# Sheet1_Overview.net
KiCad netlist of a schematic drawn in Altium Designer
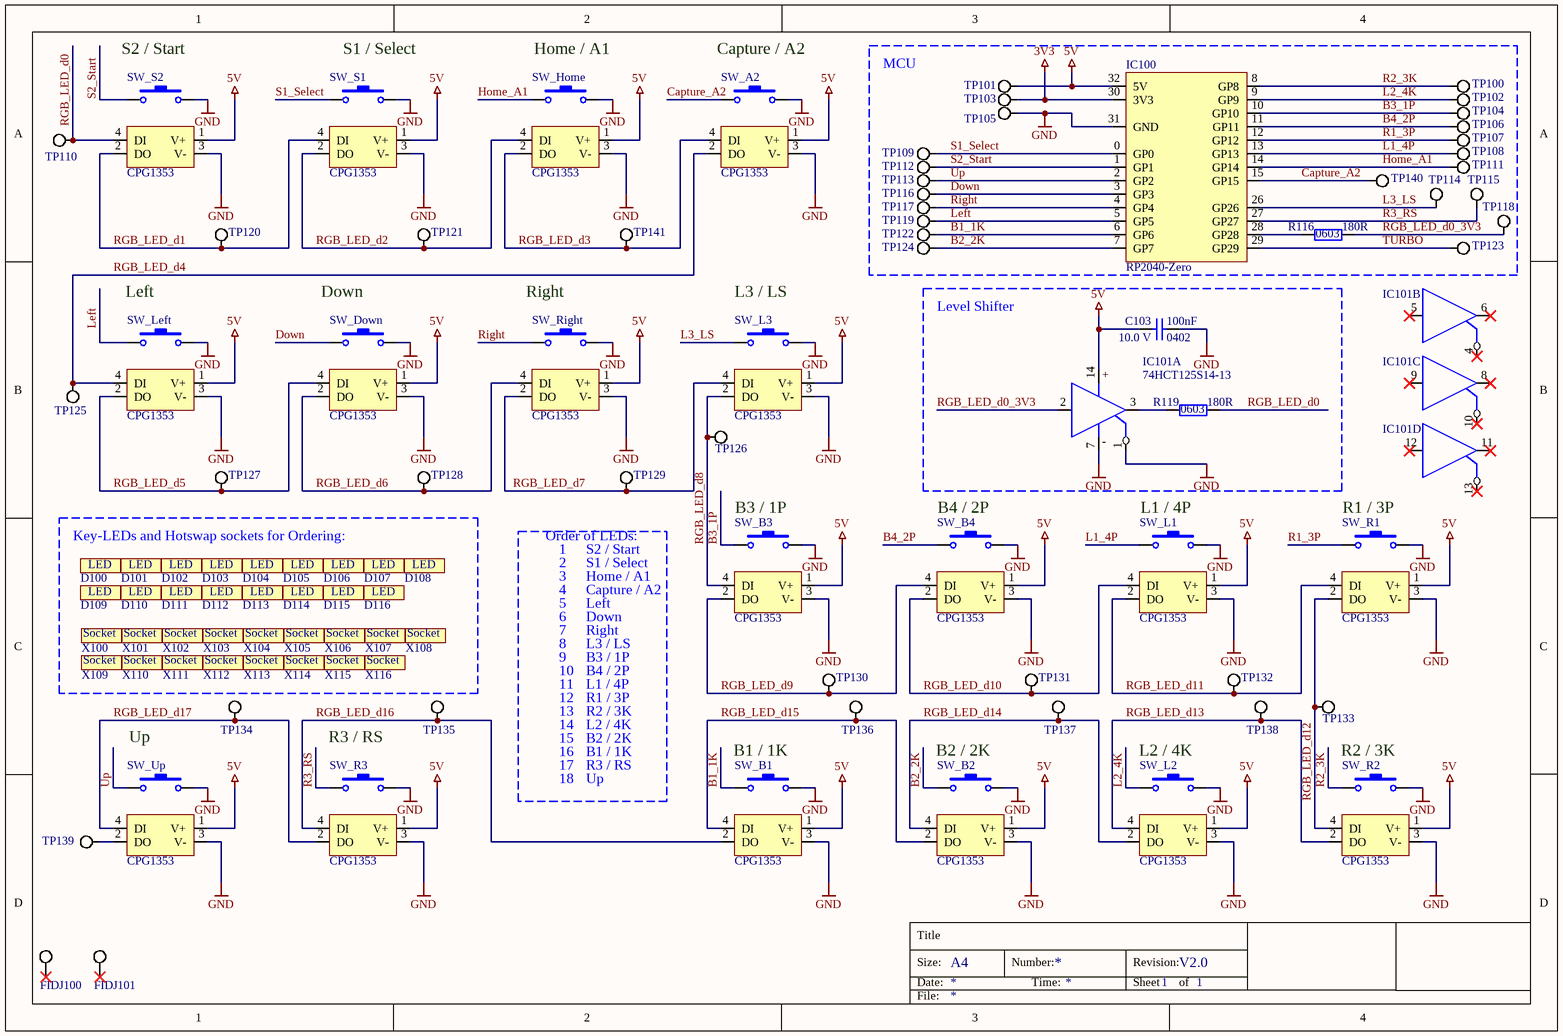
[diagram p0: Sheet1_Overview.SchDoc]

(export (version "E")
  (design (tool "Eeschema 10.0.6"))
  (components
    (comp (ref "C103")
      (value "C 100nF 0402 10V")
      (footprint "0402")
      (description "CAP CER 0.1UF 10V X5R 0402")
      (fields
        (field (name "MANUFACTURER") "Samsung Electro-Mechanics")
        (field (name "MANUFACTURER PART NUMBER") "CL05A104MP5NNNC")
        (field (name "CAPACITANCE") "100nF")
        (field (name "VOLTAGE") "10.0 V")
      )
      (libsource (lib "CS_Part_Library") (part "CAP_100nF_10V_0402"))
    )
    (comp (ref "D100")
      (value "LED RGB")
      (description "LED for SW_CPG1353")
      (fields (field (name "MANUFACTURER") "Opsco") (field (name "MANUFACTURER PART NUMBER") "SK6812Mini-E"))
      (libsource (lib "Symbols") (part "SW_CPG1353_LED"))
    )
    (comp (ref "D101")
      (value "LED RGB")
      (description "LED for SW_CPG1353")
      (fields (field (name "MANUFACTURER") "Opsco") (field (name "MANUFACTURER PART NUMBER") "SK6812Mini-E"))
      (libsource (lib "Symbols") (part "SW_CPG1353_LED"))
    )
    (comp (ref "D102")
      (value "LED RGB")
      (description "LED for SW_CPG1353")
      (fields (field (name "MANUFACTURER") "Opsco") (field (name "MANUFACTURER PART NUMBER") "SK6812Mini-E"))
      (libsource (lib "Symbols") (part "SW_CPG1353_LED"))
    )
    (comp (ref "D103")
      (value "LED RGB")
      (description "LED for SW_CPG1353")
      (fields (field (name "MANUFACTURER") "Opsco") (field (name "MANUFACTURER PART NUMBER") "SK6812Mini-E"))
      (libsource (lib "Symbols") (part "SW_CPG1353_LED"))
    )
    (comp (ref "D104")
      (value "LED RGB")
      (description "LED for SW_CPG1353")
      (fields (field (name "MANUFACTURER") "Opsco") (field (name "MANUFACTURER PART NUMBER") "SK6812Mini-E"))
      (libsource (lib "Symbols") (part "SW_CPG1353_LED"))
    )
    (comp (ref "D105")
      (value "LED RGB")
      (description "LED for SW_CPG1353")
      (fields (field (name "MANUFACTURER") "Opsco") (field (name "MANUFACTURER PART NUMBER") "SK6812Mini-E"))
      (libsource (lib "Symbols") (part "SW_CPG1353_LED"))
    )
    (comp (ref "D106")
      (value "LED RGB")
      (description "LED for SW_CPG1353")
      (fields (field (name "MANUFACTURER") "Opsco") (field (name "MANUFACTURER PART NUMBER") "SK6812Mini-E"))
      (libsource (lib "Symbols") (part "SW_CPG1353_LED"))
    )
    (comp (ref "D107")
      (value "LED RGB")
      (description "LED for SW_CPG1353")
      (fields (field (name "MANUFACTURER") "Opsco") (field (name "MANUFACTURER PART NUMBER") "SK6812Mini-E"))
      (libsource (lib "Symbols") (part "SW_CPG1353_LED"))
    )
    (comp (ref "D108")
      (value "LED RGB")
      (description "LED for SW_CPG1353")
      (fields (field (name "MANUFACTURER") "Opsco") (field (name "MANUFACTURER PART NUMBER") "SK6812Mini-E"))
      (libsource (lib "Symbols") (part "SW_CPG1353_LED"))
    )
    (comp (ref "D109")
      (value "LED RGB")
      (description "LED for SW_CPG1353")
      (fields (field (name "MANUFACTURER") "Opsco") (field (name "MANUFACTURER PART NUMBER") "SK6812Mini-E"))
      (libsource (lib "Symbols") (part "SW_CPG1353_LED"))
    )
    (comp (ref "D110")
      (value "LED RGB")
      (description "LED for SW_CPG1353")
      (fields (field (name "MANUFACTURER") "Opsco") (field (name "MANUFACTURER PART NUMBER") "SK6812Mini-E"))
      (libsource (lib "Symbols") (part "SW_CPG1353_LED"))
    )
    (comp (ref "D111")
      (value "LED RGB")
      (description "LED for SW_CPG1353")
      (fields (field (name "MANUFACTURER") "Opsco") (field (name "MANUFACTURER PART NUMBER") "SK6812Mini-E"))
      (libsource (lib "Symbols") (part "SW_CPG1353_LED"))
    )
    (comp (ref "D112")
      (value "LED RGB")
      (description "LED for SW_CPG1353")
      (fields (field (name "MANUFACTURER") "Opsco") (field (name "MANUFACTURER PART NUMBER") "SK6812Mini-E"))
      (libsource (lib "Symbols") (part "SW_CPG1353_LED"))
    )
    (comp (ref "D113")
      (value "LED RGB")
      (description "LED for SW_CPG1353")
      (fields (field (name "MANUFACTURER") "Opsco") (field (name "MANUFACTURER PART NUMBER") "SK6812Mini-E"))
      (libsource (lib "Symbols") (part "SW_CPG1353_LED"))
    )
    (comp (ref "D114")
      (value "LED RGB")
      (description "LED for SW_CPG1353")
      (fields (field (name "MANUFACTURER") "Opsco") (field (name "MANUFACTURER PART NUMBER") "SK6812Mini-E"))
      (libsource (lib "Symbols") (part "SW_CPG1353_LED"))
    )
    (comp (ref "D115")
      (value "LED RGB")
      (description "LED for SW_CPG1353")
      (fields (field (name "MANUFACTURER") "Opsco") (field (name "MANUFACTURER PART NUMBER") "SK6812Mini-E"))
      (libsource (lib "Symbols") (part "SW_CPG1353_LED"))
    )
    (comp (ref "D116")
      (value "LED RGB")
      (description "LED for SW_CPG1353")
      (fields (field (name "MANUFACTURER") "Opsco") (field (name "MANUFACTURER PART NUMBER") "SK6812Mini-E"))
      (libsource (lib "Symbols") (part "SW_CPG1353_LED"))
    )
    (comp (ref "FIDJ100")
      (value "Fiducial")
      (footprint "FIDJ_1mm")
      (description "Fiducal 1mm")
      (libsource (lib "CS_Part_Library") (part "FIDJ_1mm"))
    )
    (comp (ref "FIDJ101")
      (value "Fiducial")
      (footprint "FIDJ_1mm")
      (description "Fiducal 1mm")
      (libsource (lib "CS_Part_Library") (part "FIDJ_1mm"))
    )
    (comp (ref "IC100")
      (value "RP2040-Zero")
      (footprint "IC_RP2040-Zero")
      (description "Waveshare RP2040-Zero Module")
      (fields (field (name "MANUFACTURER") "Waveshare"))
      (libsource (lib "CS_Part_Library") (part "IC_RP2040-Zero"))
    )
    (comp (ref "IC101")
      (value "74HCT125S14-13")
      (footprint "SOIC-14")
      (description "IC BUFFER NON-INVERT 5.5V 14SO")
      (fields (field (name "MANUFACTURER") "Diodes Incorporated"))
      (libsource (lib "CS_Part_Library") (part "IC_Logic_1BUF_4CH"))
    )
    (comp (ref "R116")
      (value "R 180R 0603")
      (footprint "0603")
      (description "RES 180 OHM 1% 1/10W 0603")
      (fields
        (field (name "MANUFACTURER") "Stackpole Electronics Inc")
        (field (name "MANUFACTURER PART NUMBER") "RMCF0603FT180R")
        (field (name "RESISTANCE") "180R")
      )
      (libsource (lib "CS_Part_Library") (part "R_180R_0603"))
    )
    (comp (ref "R119")
      (value "R 180R 0603")
      (footprint "0603")
      (description "RES 180 OHM 1% 1/10W 0603")
      (fields
        (field (name "MANUFACTURER") "Stackpole Electronics Inc")
        (field (name "MANUFACTURER PART NUMBER") "RMCF0603FT180R")
        (field (name "RESISTANCE") "180R")
      )
      (libsource (lib "CS_Part_Library") (part "R_180R_0603"))
    )
    (comp (ref "SW_A2")
      (value "CPG1353")
      (footprint "SW_Kailh_CPG1353")
      (description "Kailh Choc low profile switches V2 (CPG1353) /w Hotswap, LED")
      (fields (field (name "MANUFACTURER") "Kailh"))
      (libsource (lib "CS_Part_Library") (part "SW_CPG1353_HS_LED"))
    )
    (comp (ref "SW_B1")
      (value "CPG1353")
      (footprint "SW_Kailh_CPG1353")
      (description "Kailh Choc low profile switches V2 (CPG1353) /w Hotswap, LED")
      (fields (field (name "MANUFACTURER") "Kailh"))
      (libsource (lib "CS_Part_Library") (part "SW_CPG1353_HS_LED"))
    )
    (comp (ref "SW_B2")
      (value "CPG1353")
      (footprint "SW_Kailh_CPG1353")
      (description "Kailh Choc low profile switches V2 (CPG1353) /w Hotswap, LED")
      (fields (field (name "MANUFACTURER") "Kailh"))
      (libsource (lib "CS_Part_Library") (part "SW_CPG1353_HS_LED"))
    )
    (comp (ref "SW_B3")
      (value "CPG1353")
      (footprint "SW_Kailh_CPG1353")
      (description "Kailh Choc low profile switches V2 (CPG1353) /w Hotswap, LED")
      (fields (field (name "MANUFACTURER") "Kailh"))
      (libsource (lib "CS_Part_Library") (part "SW_CPG1353_HS_LED"))
    )
    (comp (ref "SW_B4")
      (value "CPG1353")
      (footprint "SW_Kailh_CPG1353")
      (description "Kailh Choc low profile switches V2 (CPG1353) /w Hotswap, LED")
      (fields (field (name "MANUFACTURER") "Kailh"))
      (libsource (lib "CS_Part_Library") (part "SW_CPG1353_HS_LED"))
    )
    (comp (ref "SW_Down")
      (value "CPG1353")
      (footprint "SW_Kailh_CPG1353")
      (description "Kailh Choc low profile switches V2 (CPG1353) /w Hotswap, LED")
      (fields (field (name "MANUFACTURER") "Kailh"))
      (libsource (lib "CS_Part_Library") (part "SW_CPG1353_HS_LED"))
    )
    (comp (ref "SW_Home")
      (value "CPG1353")
      (footprint "SW_Kailh_CPG1353")
      (description "Kailh Choc low profile switches V2 (CPG1353) /w Hotswap, LED")
      (fields (field (name "MANUFACTURER") "Kailh"))
      (libsource (lib "CS_Part_Library") (part "SW_CPG1353_HS_LED"))
    )
    (comp (ref "SW_L1")
      (value "CPG1353")
      (footprint "SW_Kailh_CPG1353")
      (description "Kailh Choc low profile switches V2 (CPG1353) /w Hotswap, LED")
      (fields (field (name "MANUFACTURER") "Kailh"))
      (libsource (lib "CS_Part_Library") (part "SW_CPG1353_HS_LED"))
    )
    (comp (ref "SW_L2")
      (value "CPG1353")
      (footprint "SW_Kailh_CPG1353")
      (description "Kailh Choc low profile switches V2 (CPG1353) /w Hotswap, LED")
      (fields (field (name "MANUFACTURER") "Kailh"))
      (libsource (lib "CS_Part_Library") (part "SW_CPG1353_HS_LED"))
    )
    (comp (ref "SW_L3")
      (value "CPG1353")
      (footprint "SW_Kailh_CPG1353")
      (description "Kailh Choc low profile switches V2 (CPG1353) /w Hotswap, LED")
      (fields (field (name "MANUFACTURER") "Kailh"))
      (libsource (lib "CS_Part_Library") (part "SW_CPG1353_HS_LED"))
    )
    (comp (ref "SW_Left")
      (value "CPG1353")
      (footprint "SW_Kailh_CPG1353")
      (description "Kailh Choc low profile switches V2 (CPG1353) /w Hotswap, LED")
      (fields (field (name "MANUFACTURER") "Kailh"))
      (libsource (lib "CS_Part_Library") (part "SW_CPG1353_HS_LED"))
    )
    (comp (ref "SW_R1")
      (value "CPG1353")
      (footprint "SW_Kailh_CPG1353")
      (description "Kailh Choc low profile switches V2 (CPG1353) /w Hotswap, LED")
      (fields (field (name "MANUFACTURER") "Kailh"))
      (libsource (lib "CS_Part_Library") (part "SW_CPG1353_HS_LED"))
    )
    (comp (ref "SW_R2")
      (value "CPG1353")
      (footprint "SW_Kailh_CPG1353")
      (description "Kailh Choc low profile switches V2 (CPG1353) /w Hotswap, LED")
      (fields (field (name "MANUFACTURER") "Kailh"))
      (libsource (lib "CS_Part_Library") (part "SW_CPG1353_HS_LED"))
    )
    (comp (ref "SW_R3")
      (value "CPG1353")
      (footprint "SW_Kailh_CPG1353")
      (description "Kailh Choc low profile switches V2 (CPG1353) /w Hotswap, LED")
      (fields (field (name "MANUFACTURER") "Kailh"))
      (libsource (lib "CS_Part_Library") (part "SW_CPG1353_HS_LED"))
    )
    (comp (ref "SW_Right")
      (value "CPG1353")
      (footprint "SW_Kailh_CPG1353")
      (description "Kailh Choc low profile switches V2 (CPG1353) /w Hotswap, LED")
      (fields (field (name "MANUFACTURER") "Kailh"))
      (libsource (lib "CS_Part_Library") (part "SW_CPG1353_HS_LED"))
    )
    (comp (ref "SW_S1")
      (value "CPG1353")
      (footprint "SW_Kailh_CPG1353")
      (description "Kailh Choc low profile switches V2 (CPG1353) /w Hotswap, LED")
      (fields (field (name "MANUFACTURER") "Kailh"))
      (libsource (lib "CS_Part_Library") (part "SW_CPG1353_HS_LED"))
    )
    (comp (ref "SW_S2")
      (value "CPG1353")
      (footprint "SW_Kailh_CPG1353")
      (description "Kailh Choc low profile switches V2 (CPG1353) /w Hotswap, LED")
      (fields (field (name "MANUFACTURER") "Kailh"))
      (libsource (lib "CS_Part_Library") (part "SW_CPG1353_HS_LED"))
    )
    (comp (ref "SW_Up")
      (value "CPG1353")
      (footprint "SW_Kailh_CPG1353")
      (description "Kailh Choc low profile switches V2 (CPG1353) /w Hotswap, LED")
      (fields (field (name "MANUFACTURER") "Kailh"))
      (libsource (lib "CS_Part_Library") (part "SW_CPG1353_HS_LED"))
    )
    (comp (ref "TP100")
      (value "TP")
      (footprint "TP_1mm")
      (description "Test Point 1mm")
      (libsource (lib "CS_Part_Library") (part "TP_1mm"))
    )
    (comp (ref "TP101")
      (value "TP")
      (footprint "TP_1mm")
      (description "Test Point 1mm")
      (libsource (lib "CS_Part_Library") (part "TP_1mm"))
    )
    (comp (ref "TP102")
      (value "TP")
      (footprint "TP_1mm")
      (description "Test Point 1mm")
      (libsource (lib "CS_Part_Library") (part "TP_1mm"))
    )
    (comp (ref "TP103")
      (value "TP")
      (footprint "TP_1mm")
      (description "Test Point 1mm")
      (libsource (lib "CS_Part_Library") (part "TP_1mm"))
    )
    (comp (ref "TP104")
      (value "TP")
      (footprint "TP_1mm")
      (description "Test Point 1mm")
      (libsource (lib "CS_Part_Library") (part "TP_1mm"))
    )
    (comp (ref "TP105")
      (value "TP")
      (footprint "TP_1mm")
      (description "Test Point 1mm")
      (libsource (lib "CS_Part_Library") (part "TP_1mm"))
    )
    (comp (ref "TP106")
      (value "TP")
      (footprint "TP_1mm")
      (description "Test Point 1mm")
      (libsource (lib "CS_Part_Library") (part "TP_1mm"))
    )
    (comp (ref "TP107")
      (value "TP")
      (footprint "TP_1mm")
      (description "Test Point 1mm")
      (libsource (lib "CS_Part_Library") (part "TP_1mm"))
    )
    (comp (ref "TP108")
      (value "TP")
      (footprint "TP_1mm")
      (description "Test Point 1mm")
      (libsource (lib "CS_Part_Library") (part "TP_1mm"))
    )
    (comp (ref "TP109")
      (value "TP")
      (footprint "TP_1mm")
      (description "Test Point 1mm")
      (libsource (lib "CS_Part_Library") (part "TP_1mm"))
    )
    (comp (ref "TP110")
      (value "TP")
      (footprint "TP_1mm")
      (description "Test Point 1mm")
      (libsource (lib "CS_Part_Library") (part "TP_1mm"))
    )
    (comp (ref "TP111")
      (value "TP")
      (footprint "TP_1mm")
      (description "Test Point 1mm")
      (libsource (lib "CS_Part_Library") (part "TP_1mm"))
    )
    (comp (ref "TP112")
      (value "TP")
      (footprint "TP_1mm")
      (description "Test Point 1mm")
      (libsource (lib "CS_Part_Library") (part "TP_1mm"))
    )
    (comp (ref "TP113")
      (value "TP")
      (footprint "TP_1mm")
      (description "Test Point 1mm")
      (libsource (lib "CS_Part_Library") (part "TP_1mm"))
    )
    (comp (ref "TP114")
      (value "TP")
      (footprint "TP_1mm")
      (description "Test Point 1mm")
      (libsource (lib "CS_Part_Library") (part "TP_1mm"))
    )
    (comp (ref "TP115")
      (value "TP")
      (footprint "TP_1mm")
      (description "Test Point 1mm")
      (libsource (lib "CS_Part_Library") (part "TP_1mm"))
    )
    (comp (ref "TP116")
      (value "TP")
      (footprint "TP_1mm")
      (description "Test Point 1mm")
      (libsource (lib "CS_Part_Library") (part "TP_1mm"))
    )
    (comp (ref "TP117")
      (value "TP")
      (footprint "TP_1mm")
      (description "Test Point 1mm")
      (libsource (lib "CS_Part_Library") (part "TP_1mm"))
    )
    (comp (ref "TP118")
      (value "TP")
      (footprint "TP_1mm")
      (description "Test Point 1mm")
      (libsource (lib "CS_Part_Library") (part "TP_1mm"))
    )
    (comp (ref "TP119")
      (value "TP")
      (footprint "TP_1mm")
      (description "Test Point 1mm")
      (libsource (lib "CS_Part_Library") (part "TP_1mm"))
    )
    (comp (ref "TP120")
      (value "TP")
      (footprint "TP_1mm")
      (description "Test Point 1mm")
      (libsource (lib "CS_Part_Library") (part "TP_1mm"))
    )
    (comp (ref "TP121")
      (value "TP")
      (footprint "TP_1mm")
      (description "Test Point 1mm")
      (libsource (lib "CS_Part_Library") (part "TP_1mm"))
    )
    (comp (ref "TP122")
      (value "TP")
      (footprint "TP_1mm")
      (description "Test Point 1mm")
      (libsource (lib "CS_Part_Library") (part "TP_1mm"))
    )
    (comp (ref "TP123")
      (value "TP")
      (footprint "TP_1mm")
      (description "Test Point 1mm")
      (libsource (lib "CS_Part_Library") (part "TP_1mm"))
    )
    (comp (ref "TP124")
      (value "TP")
      (footprint "TP_1mm")
      (description "Test Point 1mm")
      (libsource (lib "CS_Part_Library") (part "TP_1mm"))
    )
    (comp (ref "TP125")
      (value "TP")
      (footprint "TP_1mm")
      (description "Test Point 1mm")
      (libsource (lib "CS_Part_Library") (part "TP_1mm"))
    )
    (comp (ref "TP126")
      (value "TP")
      (footprint "TP_1mm")
      (description "Test Point 1mm")
      (libsource (lib "CS_Part_Library") (part "TP_1mm"))
    )
    (comp (ref "TP127")
      (value "TP")
      (footprint "TP_1mm")
      (description "Test Point 1mm")
      (libsource (lib "CS_Part_Library") (part "TP_1mm"))
    )
    (comp (ref "TP128")
      (value "TP")
      (footprint "TP_1mm")
      (description "Test Point 1mm")
      (libsource (lib "CS_Part_Library") (part "TP_1mm"))
    )
    (comp (ref "TP129")
      (value "TP")
      (footprint "TP_1mm")
      (description "Test Point 1mm")
      (libsource (lib "CS_Part_Library") (part "TP_1mm"))
    )
    (comp (ref "TP130")
      (value "TP")
      (footprint "TP_1mm")
      (description "Test Point 1mm")
      (libsource (lib "CS_Part_Library") (part "TP_1mm"))
    )
    (comp (ref "TP131")
      (value "TP")
      (footprint "TP_1mm")
      (description "Test Point 1mm")
      (libsource (lib "CS_Part_Library") (part "TP_1mm"))
    )
    (comp (ref "TP132")
      (value "TP")
      (footprint "TP_1mm")
      (description "Test Point 1mm")
      (libsource (lib "CS_Part_Library") (part "TP_1mm"))
    )
    (comp (ref "TP133")
      (value "TP")
      (footprint "TP_1mm")
      (description "Test Point 1mm")
      (libsource (lib "CS_Part_Library") (part "TP_1mm"))
    )
    (comp (ref "TP134")
      (value "TP")
      (footprint "TP_1mm")
      (description "Test Point 1mm")
      (libsource (lib "CS_Part_Library") (part "TP_1mm"))
    )
    (comp (ref "TP135")
      (value "TP")
      (footprint "TP_1mm")
      (description "Test Point 1mm")
      (libsource (lib "CS_Part_Library") (part "TP_1mm"))
    )
    (comp (ref "TP136")
      (value "TP")
      (footprint "TP_1mm")
      (description "Test Point 1mm")
      (libsource (lib "CS_Part_Library") (part "TP_1mm"))
    )
    (comp (ref "TP137")
      (value "TP")
      (footprint "TP_1mm")
      (description "Test Point 1mm")
      (libsource (lib "CS_Part_Library") (part "TP_1mm"))
    )
    (comp (ref "TP138")
      (value "TP")
      (footprint "TP_1mm")
      (description "Test Point 1mm")
      (libsource (lib "CS_Part_Library") (part "TP_1mm"))
    )
    (comp (ref "TP139")
      (value "TP")
      (footprint "TP_1mm")
      (description "Test Point 1mm")
      (libsource (lib "CS_Part_Library") (part "TP_1mm"))
    )
    (comp (ref "TP140")
      (value "TP")
      (footprint "TP_1mm")
      (description "Test Point 1mm")
      (libsource (lib "CS_Part_Library") (part "TP_1mm"))
    )
    (comp (ref "TP141")
      (value "TP")
      (footprint "TP_1mm")
      (description "Test Point 1mm")
      (libsource (lib "CS_Part_Library") (part "TP_1mm"))
    )
    (comp (ref "X100")
      (value "Socket")
      (description "Socket for SW_CPG1353")
      (fields (field (name "MANUFACTURER") "Kailh") (field (name "MANUFACTURER PART NUMBER") "PG1350"))
      (libsource (lib "Symbols") (part "SW_CPG1353_socket"))
    )
    (comp (ref "X101")
      (value "Socket")
      (description "Socket for SW_CPG1353")
      (fields (field (name "MANUFACTURER") "Kailh") (field (name "MANUFACTURER PART NUMBER") "PG1350"))
      (libsource (lib "Symbols") (part "SW_CPG1353_socket"))
    )
    (comp (ref "X102")
      (value "Socket")
      (description "Socket for SW_CPG1353")
      (fields (field (name "MANUFACTURER") "Kailh") (field (name "MANUFACTURER PART NUMBER") "PG1350"))
      (libsource (lib "Symbols") (part "SW_CPG1353_socket"))
    )
    (comp (ref "X103")
      (value "Socket")
      (description "Socket for SW_CPG1353")
      (fields (field (name "MANUFACTURER") "Kailh") (field (name "MANUFACTURER PART NUMBER") "PG1350"))
      (libsource (lib "Symbols") (part "SW_CPG1353_socket"))
    )
    (comp (ref "X104")
      (value "Socket")
      (description "Socket for SW_CPG1353")
      (fields (field (name "MANUFACTURER") "Kailh") (field (name "MANUFACTURER PART NUMBER") "PG1350"))
      (libsource (lib "Symbols") (part "SW_CPG1353_socket"))
    )
    (comp (ref "X105")
      (value "Socket")
      (description "Socket for SW_CPG1353")
      (fields (field (name "MANUFACTURER") "Kailh") (field (name "MANUFACTURER PART NUMBER") "PG1350"))
      (libsource (lib "Symbols") (part "SW_CPG1353_socket"))
    )
    (comp (ref "X106")
      (value "Socket")
      (description "Socket for SW_CPG1353")
      (fields (field (name "MANUFACTURER") "Kailh") (field (name "MANUFACTURER PART NUMBER") "PG1350"))
      (libsource (lib "Symbols") (part "SW_CPG1353_socket"))
    )
    (comp (ref "X107")
      (value "Socket")
      (description "Socket for SW_CPG1353")
      (fields (field (name "MANUFACTURER") "Kailh") (field (name "MANUFACTURER PART NUMBER") "PG1350"))
      (libsource (lib "Symbols") (part "SW_CPG1353_socket"))
    )
    (comp (ref "X108")
      (value "Socket")
      (description "Socket for SW_CPG1353")
      (fields (field (name "MANUFACTURER") "Kailh") (field (name "MANUFACTURER PART NUMBER") "PG1350"))
      (libsource (lib "Symbols") (part "SW_CPG1353_socket"))
    )
    (comp (ref "X109")
      (value "Socket")
      (description "Socket for SW_CPG1353")
      (fields (field (name "MANUFACTURER") "Kailh") (field (name "MANUFACTURER PART NUMBER") "PG1350"))
      (libsource (lib "Symbols") (part "SW_CPG1353_socket"))
    )
    (comp (ref "X110")
      (value "Socket")
      (description "Socket for SW_CPG1353")
      (fields (field (name "MANUFACTURER") "Kailh") (field (name "MANUFACTURER PART NUMBER") "PG1350"))
      (libsource (lib "Symbols") (part "SW_CPG1353_socket"))
    )
    (comp (ref "X111")
      (value "Socket")
      (description "Socket for SW_CPG1353")
      (fields (field (name "MANUFACTURER") "Kailh") (field (name "MANUFACTURER PART NUMBER") "PG1350"))
      (libsource (lib "Symbols") (part "SW_CPG1353_socket"))
    )
    (comp (ref "X112")
      (value "Socket")
      (description "Socket for SW_CPG1353")
      (fields (field (name "MANUFACTURER") "Kailh") (field (name "MANUFACTURER PART NUMBER") "PG1350"))
      (libsource (lib "Symbols") (part "SW_CPG1353_socket"))
    )
    (comp (ref "X113")
      (value "Socket")
      (description "Socket for SW_CPG1353")
      (fields (field (name "MANUFACTURER") "Kailh") (field (name "MANUFACTURER PART NUMBER") "PG1350"))
      (libsource (lib "Symbols") (part "SW_CPG1353_socket"))
    )
    (comp (ref "X114")
      (value "Socket")
      (description "Socket for SW_CPG1353")
      (fields (field (name "MANUFACTURER") "Kailh") (field (name "MANUFACTURER PART NUMBER") "PG1350"))
      (libsource (lib "Symbols") (part "SW_CPG1353_socket"))
    )
    (comp (ref "X115")
      (value "Socket")
      (description "Socket for SW_CPG1353")
      (fields (field (name "MANUFACTURER") "Kailh") (field (name "MANUFACTURER PART NUMBER") "PG1350"))
      (libsource (lib "Symbols") (part "SW_CPG1353_socket"))
    )
    (comp (ref "X116")
      (value "Socket")
      (description "Socket for SW_CPG1353")
      (fields (field (name "MANUFACTURER") "Kailh") (field (name "MANUFACTURER PART NUMBER") "PG1350"))
      (libsource (lib "Symbols") (part "SW_CPG1353_socket"))
    )
  )
  (nets
    (net (code "1") (name "/B1_1K") (class "Default")
      (node (ref "IC100") (pin "6") (pinfunction "GP6_6") (pintype "passive"))
      (node (ref "SW_B1") (pin "A") (pinfunction "A_A") (pintype "passive"))
      (node (ref "TP122") (pin "1") (pinfunction "TP_1") (pintype "passive"))
    )
    (net (code "2") (name "/B2_2K") (class "Default")
      (node (ref "IC100") (pin "7") (pinfunction "GP7_7") (pintype "passive"))
      (node (ref "SW_B2") (pin "A") (pinfunction "A_A") (pintype "passive"))
      (node (ref "TP124") (pin "1") (pinfunction "TP_1") (pintype "passive"))
    )
    (net (code "3") (name "/B3_1P") (class "Default")
      (node (ref "IC100") (pin "10") (pinfunction "GP10_10") (pintype "passive"))
      (node (ref "SW_B3") (pin "A") (pinfunction "A_A") (pintype "passive"))
      (node (ref "TP104") (pin "1") (pinfunction "TP_1") (pintype "passive"))
    )
    (net (code "4") (name "/B4_2P") (class "Default")
      (node (ref "IC100") (pin "11") (pinfunction "GP11_11") (pintype "passive"))
      (node (ref "SW_B4") (pin "A") (pinfunction "A_A") (pintype "passive"))
      (node (ref "TP106") (pin "1") (pinfunction "TP_1") (pintype "passive"))
    )
    (net (code "5") (name "/Capture_A2") (class "Default")
      (node (ref "IC100") (pin "15") (pinfunction "GP15_15") (pintype "passive"))
      (node (ref "SW_A2") (pin "A") (pinfunction "A_A") (pintype "passive"))
      (node (ref "TP140") (pin "1") (pinfunction "TP_1") (pintype "passive"))
    )
    (net (code "6") (name "/Down") (class "Default")
      (node (ref "IC100") (pin "3") (pinfunction "GP3_3") (pintype "passive"))
      (node (ref "SW_Down") (pin "A") (pinfunction "A_A") (pintype "passive"))
      (node (ref "TP116") (pin "1") (pinfunction "TP_1") (pintype "passive"))
    )
    (net (code "7") (name "/Home_A1") (class "Default")
      (node (ref "IC100") (pin "14") (pinfunction "GP14_14") (pintype "passive"))
      (node (ref "SW_Home") (pin "A") (pinfunction "A_A") (pintype "passive"))
      (node (ref "TP111") (pin "1") (pinfunction "TP_1") (pintype "passive"))
    )
    (net (code "8") (name "/L1_4P") (class "Default")
      (node (ref "IC100") (pin "13") (pinfunction "GP13_13") (pintype "passive"))
      (node (ref "SW_L1") (pin "A") (pinfunction "A_A") (pintype "passive"))
      (node (ref "TP108") (pin "1") (pinfunction "TP_1") (pintype "passive"))
    )
    (net (code "9") (name "/L2_4K") (class "Default")
      (node (ref "IC100") (pin "9") (pinfunction "GP9_9") (pintype "passive"))
      (node (ref "SW_L2") (pin "A") (pinfunction "A_A") (pintype "passive"))
      (node (ref "TP102") (pin "1") (pinfunction "TP_1") (pintype "passive"))
    )
    (net (code "10") (name "/L3_LS") (class "Default")
      (node (ref "IC100") (pin "26") (pinfunction "GP26_26") (pintype "passive"))
      (node (ref "SW_L3") (pin "A") (pinfunction "A_A") (pintype "passive"))
      (node (ref "TP114") (pin "1") (pinfunction "TP_1") (pintype "passive"))
    )
    (net (code "11") (name "/Left") (class "Default")
      (node (ref "IC100") (pin "5") (pinfunction "GP5_5") (pintype "passive"))
      (node (ref "SW_Left") (pin "A") (pinfunction "A_A") (pintype "passive"))
      (node (ref "TP119") (pin "1") (pinfunction "TP_1") (pintype "passive"))
    )
    (net (code "12") (name "/R1_3P") (class "Default")
      (node (ref "IC100") (pin "12") (pinfunction "GP12_12") (pintype "passive"))
      (node (ref "SW_R1") (pin "A") (pinfunction "A_A") (pintype "passive"))
      (node (ref "TP107") (pin "1") (pinfunction "TP_1") (pintype "passive"))
    )
    (net (code "13") (name "/R2_3K") (class "Default")
      (node (ref "IC100") (pin "8") (pinfunction "GP8_8") (pintype "passive"))
      (node (ref "SW_R2") (pin "A") (pinfunction "A_A") (pintype "passive"))
      (node (ref "TP100") (pin "1") (pinfunction "TP_1") (pintype "passive"))
    )
    (net (code "14") (name "/R3_RS") (class "Default")
      (node (ref "IC100") (pin "27") (pinfunction "GP27_27") (pintype "passive"))
      (node (ref "SW_R3") (pin "A") (pinfunction "A_A") (pintype "passive"))
      (node (ref "TP115") (pin "1") (pinfunction "TP_1") (pintype "passive"))
    )
    (net (code "15") (name "/RGB_LED_d0") (class "Default")
      (node (ref "R119") (pin "2") (pinfunction "2_2") (pintype "passive"))
      (node (ref "SW_S2") (pin "4") (pinfunction "DI_4") (pintype "passive"))
      (node (ref "TP110") (pin "1") (pinfunction "TP_1") (pintype "passive"))
    )
    (net (code "16") (name "/RGB_LED_d0_3V3") (class "Default")
      (node (ref "IC101") (pin "2") (pinfunction "1A_2") (pintype "passive"))
      (node (ref "R116") (pin "2") (pinfunction "2_2") (pintype "passive"))
      (node (ref "TP118") (pin "1") (pinfunction "TP_1") (pintype "passive"))
    )
    (net (code "17") (name "/RGB_LED_d1") (class "Default")
      (node (ref "SW_S1") (pin "4") (pinfunction "DI_4") (pintype "passive"))
      (node (ref "SW_S2") (pin "2") (pinfunction "DO_2") (pintype "passive"))
      (node (ref "TP120") (pin "1") (pinfunction "TP_1") (pintype "passive"))
    )
    (net (code "18") (name "/RGB_LED_d2") (class "Default")
      (node (ref "SW_Home") (pin "4") (pinfunction "DI_4") (pintype "passive"))
      (node (ref "SW_S1") (pin "2") (pinfunction "DO_2") (pintype "passive"))
      (node (ref "TP121") (pin "1") (pinfunction "TP_1") (pintype "passive"))
    )
    (net (code "19") (name "/RGB_LED_d3") (class "Default")
      (node (ref "SW_A2") (pin "4") (pinfunction "DI_4") (pintype "passive"))
      (node (ref "SW_Home") (pin "2") (pinfunction "DO_2") (pintype "passive"))
      (node (ref "TP141") (pin "1") (pinfunction "TP_1") (pintype "passive"))
    )
    (net (code "20") (name "/RGB_LED_d4") (class "Default")
      (node (ref "SW_A2") (pin "2") (pinfunction "DO_2") (pintype "passive"))
      (node (ref "SW_Left") (pin "4") (pinfunction "DI_4") (pintype "passive"))
      (node (ref "TP125") (pin "1") (pinfunction "TP_1") (pintype "passive"))
    )
    (net (code "21") (name "/RGB_LED_d5") (class "Default")
      (node (ref "SW_Down") (pin "4") (pinfunction "DI_4") (pintype "passive"))
      (node (ref "SW_Left") (pin "2") (pinfunction "DO_2") (pintype "passive"))
      (node (ref "TP127") (pin "1") (pinfunction "TP_1") (pintype "passive"))
    )
    (net (code "22") (name "/RGB_LED_d6") (class "Default")
      (node (ref "SW_Down") (pin "2") (pinfunction "DO_2") (pintype "passive"))
      (node (ref "SW_Right") (pin "4") (pinfunction "DI_4") (pintype "passive"))
      (node (ref "TP128") (pin "1") (pinfunction "TP_1") (pintype "passive"))
    )
    (net (code "23") (name "/RGB_LED_d7") (class "Default")
      (node (ref "SW_L3") (pin "4") (pinfunction "DI_4") (pintype "passive"))
      (node (ref "SW_Right") (pin "2") (pinfunction "DO_2") (pintype "passive"))
      (node (ref "TP129") (pin "1") (pinfunction "TP_1") (pintype "passive"))
    )
    (net (code "24") (name "/RGB_LED_d8") (class "Default")
      (node (ref "SW_B3") (pin "4") (pinfunction "DI_4") (pintype "passive"))
      (node (ref "SW_L3") (pin "2") (pinfunction "DO_2") (pintype "passive"))
      (node (ref "TP126") (pin "1") (pinfunction "TP_1") (pintype "passive"))
    )
    (net (code "25") (name "/RGB_LED_d9") (class "Default")
      (node (ref "SW_B3") (pin "2") (pinfunction "DO_2") (pintype "passive"))
      (node (ref "SW_B4") (pin "4") (pinfunction "DI_4") (pintype "passive"))
      (node (ref "TP130") (pin "1") (pinfunction "TP_1") (pintype "passive"))
    )
    (net (code "26") (name "/RGB_LED_d10") (class "Default")
      (node (ref "SW_B4") (pin "2") (pinfunction "DO_2") (pintype "passive"))
      (node (ref "SW_L1") (pin "4") (pinfunction "DI_4") (pintype "passive"))
      (node (ref "TP131") (pin "1") (pinfunction "TP_1") (pintype "passive"))
    )
    (net (code "27") (name "/RGB_LED_d11") (class "Default")
      (node (ref "SW_L1") (pin "2") (pinfunction "DO_2") (pintype "passive"))
      (node (ref "SW_R1") (pin "4") (pinfunction "DI_4") (pintype "passive"))
      (node (ref "TP132") (pin "1") (pinfunction "TP_1") (pintype "passive"))
    )
    (net (code "28") (name "/RGB_LED_d12") (class "Default")
      (node (ref "SW_R1") (pin "2") (pinfunction "DO_2") (pintype "passive"))
      (node (ref "SW_R2") (pin "4") (pinfunction "DI_4") (pintype "passive"))
      (node (ref "TP133") (pin "1") (pinfunction "TP_1") (pintype "passive"))
    )
    (net (code "29") (name "/RGB_LED_d13") (class "Default")
      (node (ref "SW_L2") (pin "4") (pinfunction "DI_4") (pintype "passive"))
      (node (ref "SW_R2") (pin "2") (pinfunction "DO_2") (pintype "passive"))
      (node (ref "TP138") (pin "1") (pinfunction "TP_1") (pintype "passive"))
    )
    (net (code "30") (name "/RGB_LED_d14") (class "Default")
      (node (ref "SW_B2") (pin "4") (pinfunction "DI_4") (pintype "passive"))
      (node (ref "SW_L2") (pin "2") (pinfunction "DO_2") (pintype "passive"))
      (node (ref "TP137") (pin "1") (pinfunction "TP_1") (pintype "passive"))
    )
    (net (code "31") (name "/RGB_LED_d15") (class "Default")
      (node (ref "SW_B1") (pin "4") (pinfunction "DI_4") (pintype "passive"))
      (node (ref "SW_B2") (pin "2") (pinfunction "DO_2") (pintype "passive"))
      (node (ref "TP136") (pin "1") (pinfunction "TP_1") (pintype "passive"))
    )
    (net (code "32") (name "/RGB_LED_d16") (class "Default")
      (node (ref "SW_B1") (pin "2") (pinfunction "DO_2") (pintype "passive"))
      (node (ref "SW_R3") (pin "4") (pinfunction "DI_4") (pintype "passive"))
      (node (ref "TP135") (pin "1") (pinfunction "TP_1") (pintype "passive"))
    )
    (net (code "33") (name "/RGB_LED_d17") (class "Default")
      (node (ref "SW_R3") (pin "2") (pinfunction "DO_2") (pintype "passive"))
      (node (ref "SW_Up") (pin "4") (pinfunction "DI_4") (pintype "passive"))
      (node (ref "TP134") (pin "1") (pinfunction "TP_1") (pintype "passive"))
    )
    (net (code "34") (name "/Right") (class "Default")
      (node (ref "IC100") (pin "4") (pinfunction "GP4_4") (pintype "passive"))
      (node (ref "SW_Right") (pin "A") (pinfunction "A_A") (pintype "passive"))
      (node (ref "TP117") (pin "1") (pinfunction "TP_1") (pintype "passive"))
    )
    (net (code "35") (name "/S1_Select") (class "Default")
      (node (ref "IC100") (pin "0") (pinfunction "GP0_0") (pintype "passive"))
      (node (ref "SW_S1") (pin "A") (pinfunction "A_A") (pintype "passive"))
      (node (ref "TP109") (pin "1") (pinfunction "TP_1") (pintype "passive"))
    )
    (net (code "36") (name "/S2_Start") (class "Default")
      (node (ref "IC100") (pin "1") (pinfunction "GP1_1") (pintype "passive"))
      (node (ref "SW_S2") (pin "A") (pinfunction "A_A") (pintype "passive"))
      (node (ref "TP112") (pin "1") (pinfunction "TP_1") (pintype "passive"))
    )
    (net (code "37") (name "/TURBO") (class "Default")
      (node (ref "IC100") (pin "29") (pinfunction "GP29_29") (pintype "passive"))
      (node (ref "TP123") (pin "1") (pinfunction "TP_1") (pintype "passive"))
    )
    (net (code "38") (name "/Up") (class "Default")
      (node (ref "IC100") (pin "2") (pinfunction "GP2_2") (pintype "passive"))
      (node (ref "SW_Up") (pin "A") (pinfunction "A_A") (pintype "passive"))
      (node (ref "TP113") (pin "1") (pinfunction "TP_1") (pintype "passive"))
    )
    (net (code "39") (name "3V3") (class "Default")
      (node (ref "IC100") (pin "30") (pinfunction "3V3_30") (pintype "passive"))
      (node (ref "TP103") (pin "1") (pinfunction "TP_1") (pintype "passive"))
    )
    (net (code "40") (name "5V") (class "Default")
      (node (ref "C103") (pin "1") (pinfunction "1_1") (pintype "passive"))
      (node (ref "IC100") (pin "32") (pinfunction "5V_32") (pintype "passive"))
      (node (ref "IC101") (pin "14") (pinfunction "VCC_14") (pintype "passive"))
      (node (ref "SW_A2") (pin "1") (pinfunction "V+_1") (pintype "passive"))
      (node (ref "SW_B1") (pin "1") (pinfunction "V+_1") (pintype "passive"))
      (node (ref "SW_B2") (pin "1") (pinfunction "V+_1") (pintype "passive"))
      (node (ref "SW_B3") (pin "1") (pinfunction "V+_1") (pintype "passive"))
      (node (ref "SW_B4") (pin "1") (pinfunction "V+_1") (pintype "passive"))
      (node (ref "SW_Down") (pin "1") (pinfunction "V+_1") (pintype "passive"))
      (node (ref "SW_Home") (pin "1") (pinfunction "V+_1") (pintype "passive"))
      (node (ref "SW_L1") (pin "1") (pinfunction "V+_1") (pintype "passive"))
      (node (ref "SW_L2") (pin "1") (pinfunction "V+_1") (pintype "passive"))
      (node (ref "SW_L3") (pin "1") (pinfunction "V+_1") (pintype "passive"))
      (node (ref "SW_Left") (pin "1") (pinfunction "V+_1") (pintype "passive"))
      (node (ref "SW_R1") (pin "1") (pinfunction "V+_1") (pintype "passive"))
      (node (ref "SW_R2") (pin "1") (pinfunction "V+_1") (pintype "passive"))
      (node (ref "SW_R3") (pin "1") (pinfunction "V+_1") (pintype "passive"))
      (node (ref "SW_Right") (pin "1") (pinfunction "V+_1") (pintype "passive"))
      (node (ref "SW_S1") (pin "1") (pinfunction "V+_1") (pintype "passive"))
      (node (ref "SW_S2") (pin "1") (pinfunction "V+_1") (pintype "passive"))
      (node (ref "SW_Up") (pin "1") (pinfunction "V+_1") (pintype "passive"))
      (node (ref "TP101") (pin "1") (pinfunction "TP_1") (pintype "passive"))
    )
    (net (code "41") (name "GND") (class "Default")
      (node (ref "C103") (pin "2") (pinfunction "2_2") (pintype "passive"))
      (node (ref "IC100") (pin "31") (pinfunction "GND_31") (pintype "passive"))
      (node (ref "IC101") (pin "1") (pinfunction "n1OE_1") (pintype "passive"))
      (node (ref "IC101") (pin "7") (pinfunction "GND_7") (pintype "passive"))
      (node (ref "SW_A2") (pin "3") (pinfunction "V-_3") (pintype "passive"))
      (node (ref "SW_A2") (pin "B") (pinfunction "B_B") (pintype "passive"))
      (node (ref "SW_B1") (pin "3") (pinfunction "V-_3") (pintype "passive"))
      (node (ref "SW_B1") (pin "B") (pinfunction "B_B") (pintype "passive"))
      (node (ref "SW_B2") (pin "3") (pinfunction "V-_3") (pintype "passive"))
      (node (ref "SW_B2") (pin "B") (pinfunction "B_B") (pintype "passive"))
      (node (ref "SW_B3") (pin "3") (pinfunction "V-_3") (pintype "passive"))
      (node (ref "SW_B3") (pin "B") (pinfunction "B_B") (pintype "passive"))
      (node (ref "SW_B4") (pin "3") (pinfunction "V-_3") (pintype "passive"))
      (node (ref "SW_B4") (pin "B") (pinfunction "B_B") (pintype "passive"))
      (node (ref "SW_Down") (pin "3") (pinfunction "V-_3") (pintype "passive"))
      (node (ref "SW_Down") (pin "B") (pinfunction "B_B") (pintype "passive"))
      (node (ref "SW_Home") (pin "3") (pinfunction "V-_3") (pintype "passive"))
      (node (ref "SW_Home") (pin "B") (pinfunction "B_B") (pintype "passive"))
      (node (ref "SW_L1") (pin "3") (pinfunction "V-_3") (pintype "passive"))
      (node (ref "SW_L1") (pin "B") (pinfunction "B_B") (pintype "passive"))
      (node (ref "SW_L2") (pin "3") (pinfunction "V-_3") (pintype "passive"))
      (node (ref "SW_L2") (pin "B") (pinfunction "B_B") (pintype "passive"))
      (node (ref "SW_L3") (pin "3") (pinfunction "V-_3") (pintype "passive"))
      (node (ref "SW_L3") (pin "B") (pinfunction "B_B") (pintype "passive"))
      (node (ref "SW_Left") (pin "3") (pinfunction "V-_3") (pintype "passive"))
      (node (ref "SW_Left") (pin "B") (pinfunction "B_B") (pintype "passive"))
      (node (ref "SW_R1") (pin "3") (pinfunction "V-_3") (pintype "passive"))
      (node (ref "SW_R1") (pin "B") (pinfunction "B_B") (pintype "passive"))
      (node (ref "SW_R2") (pin "3") (pinfunction "V-_3") (pintype "passive"))
      (node (ref "SW_R2") (pin "B") (pinfunction "B_B") (pintype "passive"))
      (node (ref "SW_R3") (pin "3") (pinfunction "V-_3") (pintype "passive"))
      (node (ref "SW_R3") (pin "B") (pinfunction "B_B") (pintype "passive"))
      (node (ref "SW_Right") (pin "3") (pinfunction "V-_3") (pintype "passive"))
      (node (ref "SW_Right") (pin "B") (pinfunction "B_B") (pintype "passive"))
      (node (ref "SW_S1") (pin "3") (pinfunction "V-_3") (pintype "passive"))
      (node (ref "SW_S1") (pin "B") (pinfunction "B_B") (pintype "passive"))
      (node (ref "SW_S2") (pin "3") (pinfunction "V-_3") (pintype "passive"))
      (node (ref "SW_S2") (pin "B") (pinfunction "B_B") (pintype "passive"))
      (node (ref "SW_Up") (pin "3") (pinfunction "V-_3") (pintype "passive"))
      (node (ref "SW_Up") (pin "B") (pinfunction "B_B") (pintype "passive"))
      (node (ref "TP105") (pin "1") (pinfunction "TP_1") (pintype "passive"))
    )
    (net (code "42") (name "Net-(IC100-GP28)") (class "Default")
      (node (ref "IC100") (pin "28") (pinfunction "GP28_28") (pintype "passive"))
      (node (ref "R116") (pin "1") (pinfunction "1_1") (pintype "passive"))
    )
    (net (code "43") (name "Net-(IC101A-1Y)") (class "Default")
      (node (ref "IC101") (pin "3") (pinfunction "1Y_3") (pintype "passive"))
      (node (ref "R119") (pin "1") (pinfunction "1_1") (pintype "passive"))
    )
    (net (code "44") (name "Net-(SW_Up-DO)") (class "Default")
      (node (ref "SW_Up") (pin "2") (pinfunction "DO_2") (pintype "passive"))
      (node (ref "TP139") (pin "1") (pinfunction "TP_1") (pintype "passive"))
    )
    (net (code "45") (name "unconnected-(FIDJ100-Pad1)") (class "Default")
      (node (ref "FIDJ100") (pin "1") (pinfunction "1_1") (pintype "passive+no_connect"))
    )
    (net (code "46") (name "unconnected-(FIDJ101-Pad1)") (class "Default")
      (node (ref "FIDJ101") (pin "1") (pinfunction "1_1") (pintype "passive+no_connect"))
    )
    (net (code "47") (name "unconnected-(IC101B-2A-Pad5)") (class "Default")
      (node (ref "IC101") (pin "5") (pinfunction "2A_5") (pintype "passive+no_connect"))
    )
    (net (code "48") (name "unconnected-(IC101B-2Y-Pad6)") (class "Default")
      (node (ref "IC101") (pin "6") (pinfunction "2Y_6") (pintype "passive+no_connect"))
    )
    (net (code "49") (name "unconnected-(IC101B-n2OE-Pad4)") (class "Default")
      (node (ref "IC101") (pin "4") (pinfunction "n2OE_4") (pintype "passive+no_connect"))
    )
    (net (code "50") (name "unconnected-(IC101C-3A-Pad9)") (class "Default")
      (node (ref "IC101") (pin "9") (pinfunction "3A_9") (pintype "passive+no_connect"))
    )
    (net (code "51") (name "unconnected-(IC101C-3Y-Pad8)") (class "Default")
      (node (ref "IC101") (pin "8") (pinfunction "3Y_8") (pintype "passive+no_connect"))
    )
    (net (code "52") (name "unconnected-(IC101C-n3OE-Pad10)") (class "Default")
      (node (ref "IC101") (pin "10") (pinfunction "n3OE_10") (pintype "passive+no_connect"))
    )
    (net (code "53") (name "unconnected-(IC101D-4A-Pad12)") (class "Default")
      (node (ref "IC101") (pin "12") (pinfunction "4A_12") (pintype "passive+no_connect"))
    )
    (net (code "54") (name "unconnected-(IC101D-4Y-Pad11)") (class "Default")
      (node (ref "IC101") (pin "11") (pinfunction "4Y_11") (pintype "passive+no_connect"))
    )
    (net (code "55") (name "unconnected-(IC101D-n4OE-Pad13)") (class "Default")
      (node (ref "IC101") (pin "13") (pinfunction "n4OE_13") (pintype "passive+no_connect"))
    )
  )
)
